# 8x8_led_matrix_DRIVER.net
KiCad netlist of a schematic drawn in EAGLE
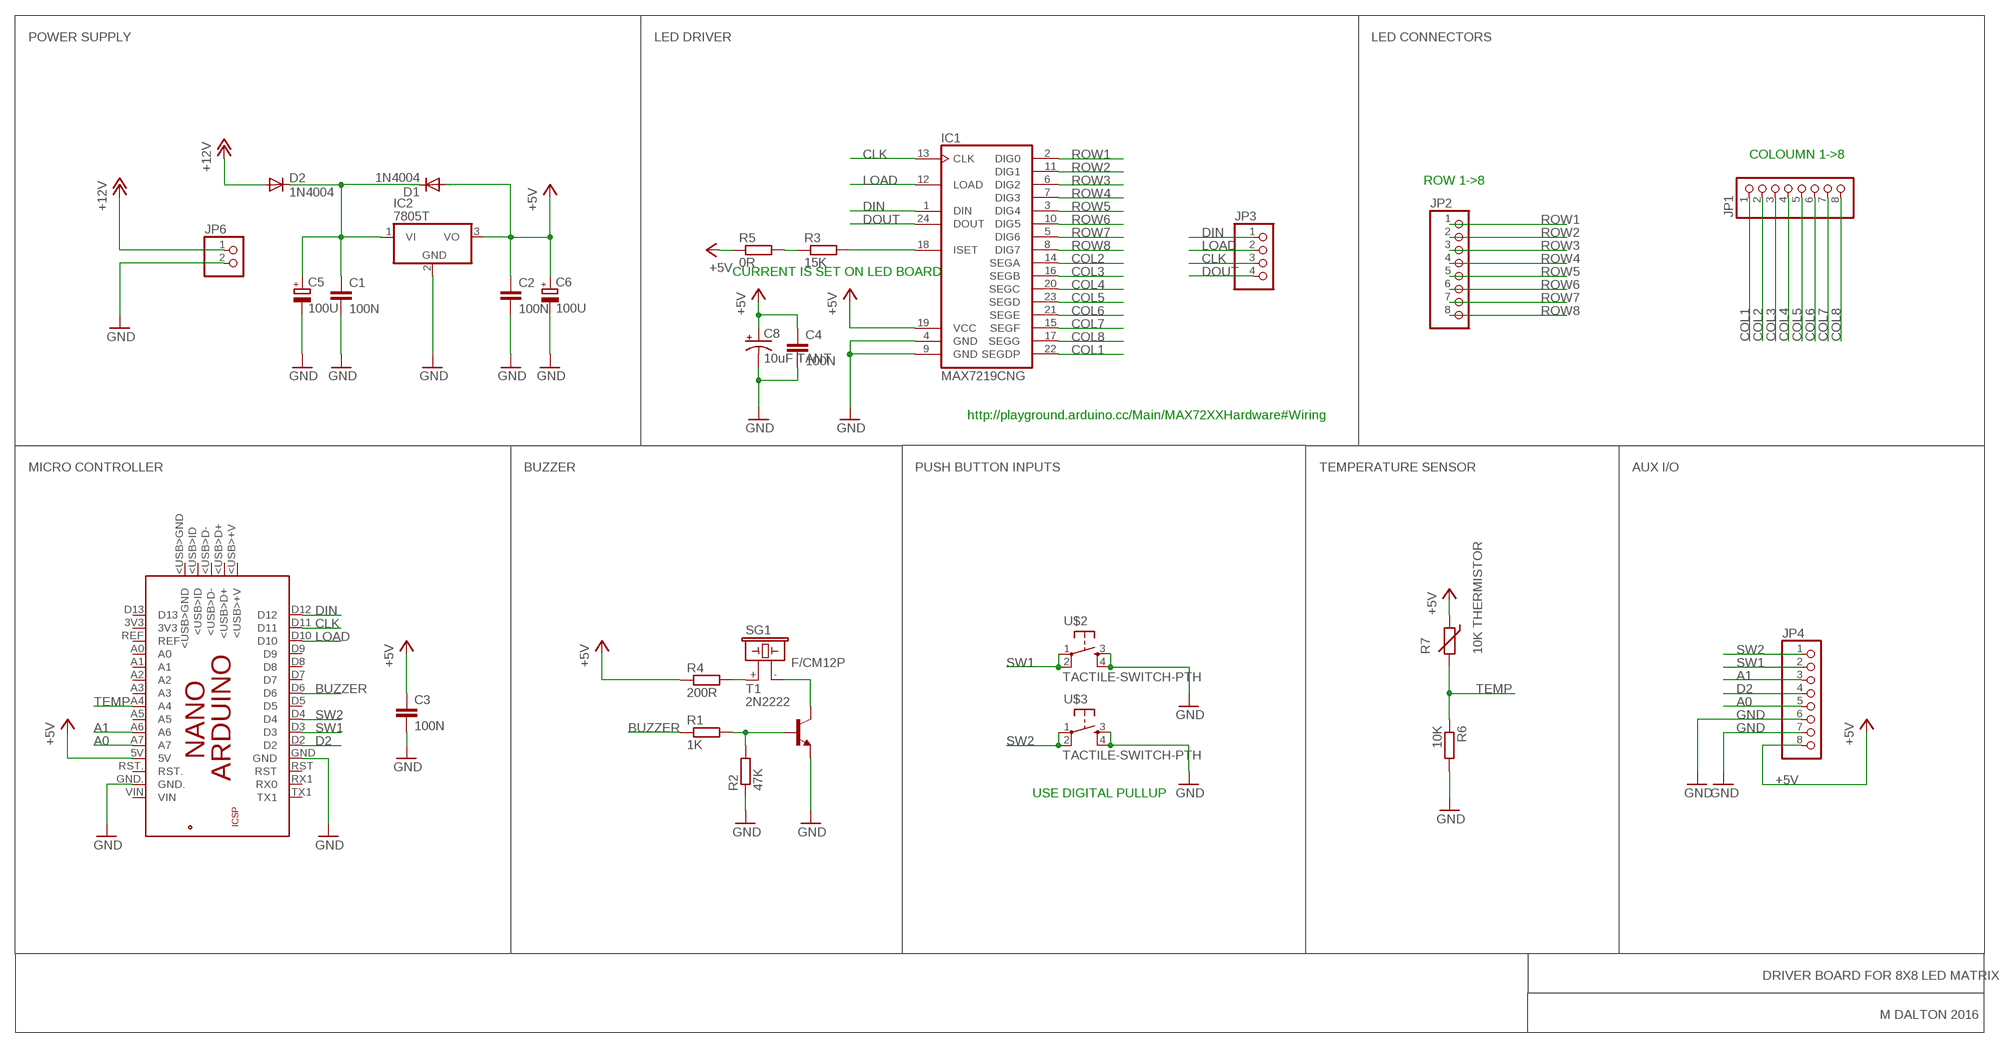
[diagram p0: schematic, sheet 1]

(export (version "E")
  (design (tool "Eeschema 10.0.6"))
  (components
    (comp (ref "C1")
      (value "100N")
      (footprint "eagle-import:C1206K")
      (libsource (lib "eagle-import") (part "C-EUC1206K"))
    )
    (comp (ref "C2")
      (value "100N")
      (footprint "eagle-import:C1206K")
      (libsource (lib "eagle-import") (part "C-EUC1206K"))
    )
    (comp (ref "C3")
      (value "100N")
      (footprint "eagle-import:C1206K")
      (libsource (lib "eagle-import") (part "C-EUC1206K"))
    )
    (comp (ref "C4")
      (value "100N")
      (footprint "eagle-import:C1206K")
      (libsource (lib "eagle-import") (part "C-EUC1206K"))
    )
    (comp (ref "C5")
      (value "100U")
      (footprint "eagle-import:E5-10,5")
      (libsource (lib "eagle-import") (part "CPOL-EUE5-10.5"))
    )
    (comp (ref "C6")
      (value "100U")
      (footprint "eagle-import:E5-10,5")
      (libsource (lib "eagle-import") (part "CPOL-EUE5-10.5"))
    )
    (comp (ref "C8")
      (value "10uF TANT")
      (footprint "eagle-import:EIA3216")
      (libsource (lib "eagle-import") (part "10UF-TANT"))
    )
    (comp (ref "D1")
      (value "1N4004")
      (footprint "eagle-import:DO41-10")
      (libsource (lib "eagle-import") (part "diode_1N4004"))
    )
    (comp (ref "D2")
      (value "1N4004")
      (footprint "eagle-import:DO41-10")
      (libsource (lib "eagle-import") (part "1N4004"))
    )
    (comp (ref "IC1")
      (value "MAX7219CNG")
      (footprint "eagle-import:DIL24-3")
      (fields (field (name "MF") "MAXIM"))
      (libsource (lib "eagle-import") (part "MAX7219CNG"))
    )
    (comp (ref "IC2")
      (value "7805T")
      (footprint "eagle-import:TO220H")
      (libsource (lib "eagle-import") (part "78T05"))
    )
    (comp (ref "JP1")
      (value "PINHD-1X8")
      (footprint "eagle-import:1X08")
      (libsource (lib "eagle-import") (part "PINHD-1X8"))
    )
    (comp (ref "JP2")
      (value "PINHD-1X8")
      (footprint "eagle-import:1X08")
      (libsource (lib "eagle-import") (part "PINHD-1X8"))
    )
    (comp (ref "JP3")
      (value "PINHD-1X4")
      (footprint "eagle-import:1X04")
      (libsource (lib "eagle-import") (part "PINHD-1X4"))
    )
    (comp (ref "JP4")
      (value "PINHD-1X8")
      (footprint "eagle-import:1X08")
      (libsource (lib "eagle-import") (part "PINHD-1X8"))
    )
    (comp (ref "JP6")
      (value "PINHD-1X2")
      (footprint "eagle-import:1X02")
      (libsource (lib "eagle-import") (part "PINHD-1X2"))
    )
    (comp (ref "PCB1")
      (value "ARDUINO_NANO")
      (footprint "eagle-import:ARDUINO_NANO")
      (libsource (lib "eagle-import") (part "ARDUINO_NANO"))
    )
    (comp (ref "R1")
      (value "1K")
      (footprint "eagle-import:M1206")
      (libsource (lib "eagle-import") (part "R-EU_M1206"))
    )
    (comp (ref "R2")
      (value "47K")
      (footprint "eagle-import:M1206")
      (libsource (lib "eagle-import") (part "R-EU_M1206"))
    )
    (comp (ref "R3")
      (value "15K")
      (footprint "eagle-import:M0805")
      (libsource (lib "eagle-import") (part "R-EU_M0805"))
    )
    (comp (ref "R4")
      (value "200R")
      (footprint "eagle-import:M1206")
      (libsource (lib "eagle-import") (part "R-EU_M1206"))
    )
    (comp (ref "R5")
      (value "0R")
      (footprint "eagle-import:M0805")
      (libsource (lib "eagle-import") (part "R-EU_M0805"))
    )
    (comp (ref "R6")
      (value "10K")
      (footprint "eagle-import:M1206")
      (libsource (lib "eagle-import") (part "R-EU_M1206"))
    )
    (comp (ref "R7")
      (value "10K THERMISTOR")
      (footprint "eagle-import:R-7,5")
      (libsource (lib "eagle-import") (part "THERMISTOR-7,5"))
    )
    (comp (ref "SG1")
      (value "F/CM12P")
      (footprint "eagle-import:F_CM12P")
      (libsource (lib "eagle-import") (part "F/CM12P"))
    )
    (comp (ref "T1")
      (value "2N2222")
      (footprint "eagle-import:TO92-EBC-OVAL")
      (libsource (lib "eagle-import") (part "2N2222"))
    )
    (comp (ref "U$2")
      (value "TACTILE-SWITCH-PTH")
      (footprint "eagle-import:TAC-SWITCH-PTH")
      (libsource (lib "eagle-import") (part "TACTILE-SWITCH-PTH"))
    )
    (comp (ref "U$3")
      (value "TACTILE-SWITCH-PTH")
      (footprint "eagle-import:TAC-SWITCH-PTH")
      (libsource (lib "eagle-import") (part "TACTILE-SWITCH-PTH"))
    )
  )
  (nets
    (net (code "1") (name "+5V") (class "Default")
      (node (ref "C2") (pin "1") (pinfunction "1_1") (pintype "passive"))
      (node (ref "C3") (pin "1") (pinfunction "1_1") (pintype "passive"))
      (node (ref "C4") (pin "1") (pinfunction "1_1") (pintype "passive"))
      (node (ref "C6") (pin "+") (pinfunction "+_+") (pintype "passive"))
      (node (ref "C8") (pin "A") (pinfunction "+_A") (pintype "passive"))
      (node (ref "D1") (pin "A") (pinfunction "A_A") (pintype "passive"))
      (node (ref "IC1") (pin "19") (pinfunction "VCC_19") (pintype "power_in"))
      (node (ref "IC2") (pin "3") (pinfunction "VO_3") (pintype "passive"))
      (node (ref "JP4") (pin "8") (pinfunction "8_8") (pintype "passive"))
      (node (ref "PCB1") (pin "5V") (pinfunction "5V_5V") (pintype "bidirectional"))
      (node (ref "R4") (pin "1") (pinfunction "1_1") (pintype "passive"))
      (node (ref "R5") (pin "1") (pinfunction "1_1") (pintype "passive"))
      (node (ref "R7") (pin "1") (pinfunction "1_1") (pintype "passive"))
    )
    (net (code "2") (name "+12V") (class "Default")
      (node (ref "D2") (pin "A") (pinfunction "A_A") (pintype "passive"))
      (node (ref "JP6") (pin "1") (pinfunction "1_1") (pintype "passive"))
    )
    (net (code "3") (name "/A0") (class "Default")
      (node (ref "JP4") (pin "5") (pinfunction "5_5") (pintype "passive"))
      (node (ref "PCB1") (pin "A7") (pinfunction "A7_A7") (pintype "bidirectional"))
    )
    (net (code "4") (name "/A1") (class "Default")
      (node (ref "JP4") (pin "3") (pinfunction "3_3") (pintype "passive"))
      (node (ref "PCB1") (pin "A6") (pinfunction "A6_A6") (pintype "bidirectional"))
    )
    (net (code "5") (name "/BUZZER") (class "Default")
      (node (ref "PCB1") (pin "D6") (pinfunction "D6_D6") (pintype "bidirectional"))
      (node (ref "R1") (pin "1") (pinfunction "1_1") (pintype "passive"))
    )
    (net (code "6") (name "/CLK") (class "Default")
      (node (ref "IC1") (pin "13") (pinfunction "CLK_13") (pintype "input"))
      (node (ref "JP3") (pin "3") (pinfunction "3_3") (pintype "passive"))
      (node (ref "PCB1") (pin "D11") (pinfunction "D11_D11") (pintype "bidirectional"))
    )
    (net (code "7") (name "/COL1") (class "Default")
      (node (ref "IC1") (pin "22") (pinfunction "SEGDP_22") (pintype "output"))
      (node (ref "JP1") (pin "1") (pinfunction "1_1") (pintype "passive"))
    )
    (net (code "8") (name "/COL2") (class "Default")
      (node (ref "IC1") (pin "14") (pinfunction "SEGA_14") (pintype "output"))
      (node (ref "JP1") (pin "2") (pinfunction "2_2") (pintype "passive"))
    )
    (net (code "9") (name "/COL3") (class "Default")
      (node (ref "IC1") (pin "16") (pinfunction "SEGB_16") (pintype "output"))
      (node (ref "JP1") (pin "3") (pinfunction "3_3") (pintype "passive"))
    )
    (net (code "10") (name "/COL4") (class "Default")
      (node (ref "IC1") (pin "20") (pinfunction "SEGC_20") (pintype "output"))
      (node (ref "JP1") (pin "4") (pinfunction "4_4") (pintype "passive"))
    )
    (net (code "11") (name "/COL5") (class "Default")
      (node (ref "IC1") (pin "23") (pinfunction "SEGD_23") (pintype "output"))
      (node (ref "JP1") (pin "5") (pinfunction "5_5") (pintype "passive"))
    )
    (net (code "12") (name "/COL6") (class "Default")
      (node (ref "IC1") (pin "21") (pinfunction "SEGE_21") (pintype "output"))
      (node (ref "JP1") (pin "6") (pinfunction "6_6") (pintype "passive"))
    )
    (net (code "13") (name "/COL7") (class "Default")
      (node (ref "IC1") (pin "15") (pinfunction "SEGF_15") (pintype "output"))
      (node (ref "JP1") (pin "7") (pinfunction "7_7") (pintype "passive"))
    )
    (net (code "14") (name "/COL8") (class "Default")
      (node (ref "IC1") (pin "17") (pinfunction "SEGG_17") (pintype "output"))
      (node (ref "JP1") (pin "8") (pinfunction "8_8") (pintype "passive"))
    )
    (net (code "15") (name "/D2") (class "Default")
      (node (ref "JP4") (pin "4") (pinfunction "4_4") (pintype "passive"))
      (node (ref "PCB1") (pin "D2") (pinfunction "D2_D2") (pintype "bidirectional"))
    )
    (net (code "16") (name "/DIN") (class "Default")
      (node (ref "IC1") (pin "1") (pinfunction "DIN_1") (pintype "input"))
      (node (ref "JP3") (pin "1") (pinfunction "1_1") (pintype "passive"))
      (node (ref "PCB1") (pin "D12") (pinfunction "D12_D12") (pintype "bidirectional"))
    )
    (net (code "17") (name "/DOUT") (class "Default")
      (node (ref "IC1") (pin "24") (pinfunction "DOUT_24") (pintype "output"))
      (node (ref "JP3") (pin "4") (pinfunction "4_4") (pintype "passive"))
    )
    (net (code "18") (name "/LOAD") (class "Default")
      (node (ref "IC1") (pin "12") (pinfunction "LOAD_12") (pintype "input"))
      (node (ref "JP3") (pin "2") (pinfunction "2_2") (pintype "passive"))
      (node (ref "PCB1") (pin "D10") (pinfunction "D10_D10") (pintype "bidirectional"))
    )
    (net (code "19") (name "/ROW1") (class "Default")
      (node (ref "IC1") (pin "2") (pinfunction "DIG0_2") (pintype "output"))
      (node (ref "JP2") (pin "1") (pinfunction "1_1") (pintype "passive"))
    )
    (net (code "20") (name "/ROW2") (class "Default")
      (node (ref "IC1") (pin "11") (pinfunction "DIG1_11") (pintype "output"))
      (node (ref "JP2") (pin "2") (pinfunction "2_2") (pintype "passive"))
    )
    (net (code "21") (name "/ROW3") (class "Default")
      (node (ref "IC1") (pin "6") (pinfunction "DIG2_6") (pintype "output"))
      (node (ref "JP2") (pin "3") (pinfunction "3_3") (pintype "passive"))
    )
    (net (code "22") (name "/ROW4") (class "Default")
      (node (ref "IC1") (pin "7") (pinfunction "DIG3_7") (pintype "output"))
      (node (ref "JP2") (pin "4") (pinfunction "4_4") (pintype "passive"))
    )
    (net (code "23") (name "/ROW5") (class "Default")
      (node (ref "IC1") (pin "3") (pinfunction "DIG4_3") (pintype "output"))
      (node (ref "JP2") (pin "5") (pinfunction "5_5") (pintype "passive"))
    )
    (net (code "24") (name "/ROW6") (class "Default")
      (node (ref "IC1") (pin "10") (pinfunction "DIG5_10") (pintype "output"))
      (node (ref "JP2") (pin "6") (pinfunction "6_6") (pintype "passive"))
    )
    (net (code "25") (name "/ROW7") (class "Default")
      (node (ref "IC1") (pin "5") (pinfunction "DIG6_5") (pintype "output"))
      (node (ref "JP2") (pin "7") (pinfunction "7_7") (pintype "passive"))
    )
    (net (code "26") (name "/ROW8") (class "Default")
      (node (ref "IC1") (pin "8") (pinfunction "DIG7_8") (pintype "output"))
      (node (ref "JP2") (pin "8") (pinfunction "8_8") (pintype "passive"))
    )
    (net (code "27") (name "/SW1") (class "Default")
      (node (ref "JP4") (pin "2") (pinfunction "2_2") (pintype "passive"))
      (node (ref "PCB1") (pin "D3") (pinfunction "D3_D3") (pintype "bidirectional"))
      (node (ref "U$2") (pin "1") (pinfunction "1_1") (pintype "passive"))
      (node (ref "U$2") (pin "2") (pinfunction "2_2") (pintype "passive"))
    )
    (net (code "28") (name "/SW2") (class "Default")
      (node (ref "JP4") (pin "1") (pinfunction "1_1") (pintype "passive"))
      (node (ref "PCB1") (pin "D4") (pinfunction "D4_D4") (pintype "bidirectional"))
      (node (ref "U$3") (pin "1") (pinfunction "1_1") (pintype "passive"))
      (node (ref "U$3") (pin "2") (pinfunction "2_2") (pintype "passive"))
    )
    (net (code "29") (name "/TEMP") (class "Default")
      (node (ref "PCB1") (pin "A4") (pinfunction "A4_A4") (pintype "bidirectional"))
      (node (ref "R6") (pin "1") (pinfunction "1_1") (pintype "passive"))
      (node (ref "R7") (pin "2") (pinfunction "2_2") (pintype "passive"))
    )
    (net (code "30") (name "GND") (class "Default")
      (node (ref "C1") (pin "2") (pinfunction "2_2") (pintype "passive"))
      (node (ref "C2") (pin "2") (pinfunction "2_2") (pintype "passive"))
      (node (ref "C3") (pin "2") (pinfunction "2_2") (pintype "passive"))
      (node (ref "C4") (pin "2") (pinfunction "2_2") (pintype "passive"))
      (node (ref "C5") (pin "-") (pinfunction "-_-") (pintype "passive"))
      (node (ref "C6") (pin "-") (pinfunction "-_-") (pintype "passive"))
      (node (ref "C8") (pin "C") (pinfunction "-_C") (pintype "passive"))
      (node (ref "IC1") (pin "4") (pinfunction "GND_4") (pintype "power_in"))
      (node (ref "IC1") (pin "9") (pinfunction "GND_9") (pintype "power_in"))
      (node (ref "IC2") (pin "2") (pinfunction "GND_2") (pintype "passive"))
      (node (ref "JP4") (pin "6") (pinfunction "6_6") (pintype "passive"))
      (node (ref "JP4") (pin "7") (pinfunction "7_7") (pintype "passive"))
      (node (ref "JP6") (pin "2") (pinfunction "2_2") (pintype "passive"))
      (node (ref "PCB1") (pin "GND") (pinfunction "GND_GND") (pintype "bidirectional"))
      (node (ref "PCB1") (pin "GND.") (pinfunction "GND._GND.") (pintype "bidirectional"))
      (node (ref "R2") (pin "1") (pinfunction "1_1") (pintype "passive"))
      (node (ref "R6") (pin "2") (pinfunction "2_2") (pintype "passive"))
      (node (ref "T1") (pin "E") (pinfunction "E_E") (pintype "passive"))
      (node (ref "U$2") (pin "3") (pinfunction "3_3") (pintype "passive"))
      (node (ref "U$2") (pin "4") (pinfunction "4_4") (pintype "passive"))
      (node (ref "U$3") (pin "3") (pinfunction "3_3") (pintype "passive"))
      (node (ref "U$3") (pin "4") (pinfunction "4_4") (pintype "passive"))
    )
    (net (code "31") (name "Net-(IC1-ISET)") (class "Default")
      (node (ref "IC1") (pin "18") (pinfunction "ISET_18") (pintype "input"))
      (node (ref "R3") (pin "2") (pinfunction "2_2") (pintype "passive"))
    )
    (net (code "32") (name "Net-(IC2-VI)") (class "Default")
      (node (ref "C1") (pin "1") (pinfunction "1_1") (pintype "passive"))
      (node (ref "C5") (pin "+") (pinfunction "+_+") (pintype "passive"))
      (node (ref "D1") (pin "C") (pinfunction "C_C") (pintype "passive"))
      (node (ref "D2") (pin "C") (pinfunction "C_C") (pintype "passive"))
      (node (ref "IC2") (pin "1") (pinfunction "VI_1") (pintype "input"))
    )
    (net (code "33") (name "Net-(R1-Pad2)") (class "Default")
      (node (ref "R1") (pin "2") (pinfunction "2_2") (pintype "passive"))
      (node (ref "R2") (pin "2") (pinfunction "2_2") (pintype "passive"))
      (node (ref "T1") (pin "B") (pinfunction "B_B") (pintype "passive"))
    )
    (net (code "34") (name "Net-(R3-Pad1)") (class "Default")
      (node (ref "R3") (pin "1") (pinfunction "1_1") (pintype "passive"))
      (node (ref "R5") (pin "2") (pinfunction "2_2") (pintype "passive"))
    )
    (net (code "35") (name "Net-(SG1-1)") (class "Default")
      (node (ref "R4") (pin "2") (pinfunction "2_2") (pintype "passive"))
      (node (ref "SG1") (pin "+") (pinfunction "1_+") (pintype "passive"))
    )
    (net (code "36") (name "Net-(SG1-2)") (class "Default")
      (node (ref "SG1") (pin "-") (pinfunction "2_-") (pintype "passive"))
      (node (ref "T1") (pin "C") (pinfunction "C_C") (pintype "passive"))
    )
    (net (code "37") (name "unconnected-(PCB1-Pad3V3)") (class "Default")
      (node (ref "PCB1") (pin "3V3") (pinfunction "3V3_3V3") (pintype "bidirectional"))
    )
    (net (code "38") (name "unconnected-(PCB1-Pad5V.)") (class "Default")
      (node (ref "PCB1") (pin "5V.") (pinfunction "5V._5V.") (pintype "bidirectional"))
    )
    (net (code "39") (name "unconnected-(PCB1-Pad<USB>+V)") (class "Default")
      (node (ref "PCB1") (pin "<USB>+V") (pinfunction "<USB>+V_<USB>+V") (pintype "bidirectional"))
    )
    (net (code "40") (name "unconnected-(PCB1-Pad<USB>D+)") (class "Default")
      (node (ref "PCB1") (pin "<USB>D+") (pinfunction "<USB>D+_<USB>D+") (pintype "bidirectional"))
    )
    (net (code "41") (name "unconnected-(PCB1-Pad<USB>D-)") (class "Default")
      (node (ref "PCB1") (pin "<USB>D-") (pinfunction "<USB>D-_<USB>D-") (pintype "bidirectional"))
    )
    (net (code "42") (name "unconnected-(PCB1-Pad<USB>GND)") (class "Default")
      (node (ref "PCB1") (pin "<USB>GND") (pinfunction "<USB>GND_<USB>GND") (pintype "bidirectional"))
    )
    (net (code "43") (name "unconnected-(PCB1-Pad<USB>ID)") (class "Default")
      (node (ref "PCB1") (pin "<USB>ID") (pinfunction "<USB>ID_<USB>ID") (pintype "bidirectional"))
    )
    (net (code "44") (name "unconnected-(PCB1-PadA0)") (class "Default")
      (node (ref "PCB1") (pin "A0") (pinfunction "A0_A0") (pintype "bidirectional"))
    )
    (net (code "45") (name "unconnected-(PCB1-PadA1)") (class "Default")
      (node (ref "PCB1") (pin "A1") (pinfunction "A1_A1") (pintype "bidirectional"))
    )
    (net (code "46") (name "unconnected-(PCB1-PadA2)") (class "Default")
      (node (ref "PCB1") (pin "A2") (pinfunction "A2_A2") (pintype "bidirectional"))
    )
    (net (code "47") (name "unconnected-(PCB1-PadA3)") (class "Default")
      (node (ref "PCB1") (pin "A3") (pinfunction "A3_A3") (pintype "bidirectional"))
    )
    (net (code "48") (name "unconnected-(PCB1-PadA5)") (class "Default")
      (node (ref "PCB1") (pin "A5") (pinfunction "A5_A5") (pintype "bidirectional"))
    )
    (net (code "49") (name "unconnected-(PCB1-PadD5)") (class "Default")
      (node (ref "PCB1") (pin "D5") (pinfunction "D5_D5") (pintype "bidirectional"))
    )
    (net (code "50") (name "unconnected-(PCB1-PadD7)") (class "Default")
      (node (ref "PCB1") (pin "D7") (pinfunction "D7_D7") (pintype "bidirectional"))
    )
    (net (code "51") (name "unconnected-(PCB1-PadD8)") (class "Default")
      (node (ref "PCB1") (pin "D8") (pinfunction "D8_D8") (pintype "bidirectional"))
    )
    (net (code "52") (name "unconnected-(PCB1-PadD9)") (class "Default")
      (node (ref "PCB1") (pin "D9") (pinfunction "D9_D9") (pintype "bidirectional"))
    )
    (net (code "53") (name "unconnected-(PCB1-PadD13)") (class "Default")
      (node (ref "PCB1") (pin "D13") (pinfunction "D13_D13") (pintype "bidirectional"))
    )
    (net (code "54") (name "unconnected-(PCB1-PadGND_)") (class "Default")
      (node (ref "PCB1") (pin "GND_") (pinfunction "GND__GND_") (pintype "bidirectional"))
    )
    (net (code "55") (name "unconnected-(PCB1-PadMISO)") (class "Default")
      (node (ref "PCB1") (pin "MISO") (pinfunction "MISO_MISO") (pintype "bidirectional"))
    )
    (net (code "56") (name "unconnected-(PCB1-PadMOSI)") (class "Default")
      (node (ref "PCB1") (pin "MOSI") (pinfunction "MOSI_MOSI") (pintype "bidirectional"))
    )
    (net (code "57") (name "unconnected-(PCB1-PadREF)") (class "Default")
      (node (ref "PCB1") (pin "REF") (pinfunction "REF_REF") (pintype "bidirectional"))
    )
    (net (code "58") (name "unconnected-(PCB1-PadRESET..)") (class "Default")
      (node (ref "PCB1") (pin "RESET..") (pinfunction "RESET.._RESET..") (pintype "bidirectional"))
    )
    (net (code "59") (name "unconnected-(PCB1-PadRST)") (class "Default")
      (node (ref "PCB1") (pin "RST") (pinfunction "RST_RST") (pintype "bidirectional"))
    )
    (net (code "60") (name "unconnected-(PCB1-PadRST.)") (class "Default")
      (node (ref "PCB1") (pin "RST.") (pinfunction "RST._RST.") (pintype "bidirectional"))
    )
    (net (code "61") (name "unconnected-(PCB1-PadSCK)") (class "Default")
      (node (ref "PCB1") (pin "SCK") (pinfunction "SCK_SCK") (pintype "bidirectional"))
    )
    (net (code "62") (name "unconnected-(PCB1-PadTX1)") (class "Default")
      (node (ref "PCB1") (pin "TX1") (pinfunction "TX1_TX1") (pintype "bidirectional"))
    )
    (net (code "63") (name "unconnected-(PCB1-PadVIN)") (class "Default")
      (node (ref "PCB1") (pin "VIN") (pinfunction "VIN_VIN") (pintype "bidirectional"))
    )
    (net (code "64") (name "unconnected-(PCB1-RX0-PadRX1)") (class "Default")
      (node (ref "PCB1") (pin "RX1") (pinfunction "RX0_RX1") (pintype "bidirectional"))
    )
  )
)
